# controls.net
KiCad netlist of a schematic drawn in Altium Designer
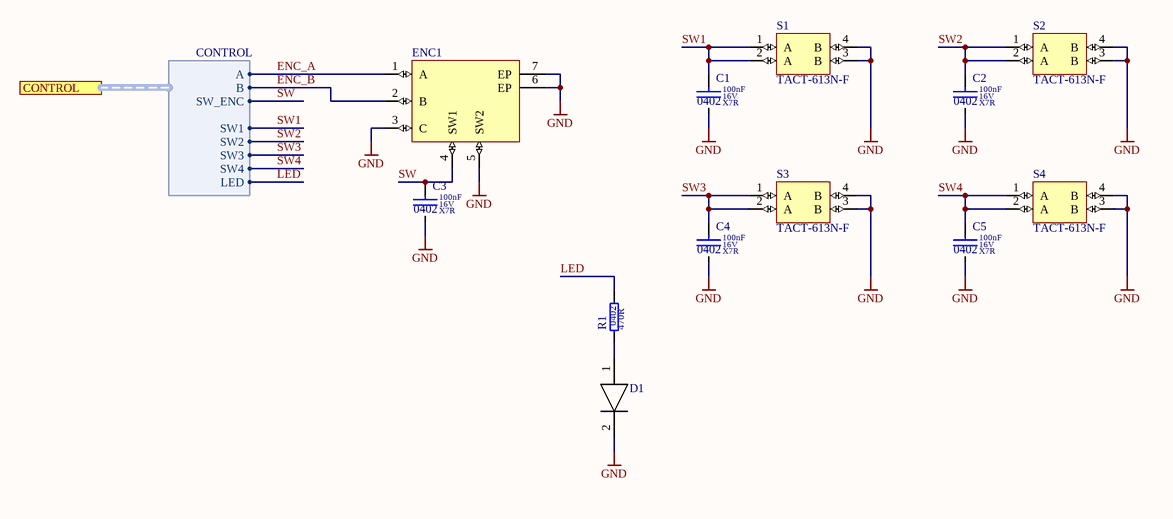
[diagram p0: controls.SchDoc]

(export (version "E")
  (design (tool "Eeschema 10.0.6"))
  (components
    (comp (ref "C1")
      (value "100nF")
      (footprint "C_0402_1005")
      (description "Capacitor")
      (fields
        (field (name "DIELECTRIC") "X7R")
        (field (name "VOLTAGE") "16V")
        (field (name "SCH_FOOTPRINT") "0402")
        (field (name "PART NUMBER") "C_100nF_16V_X7R_0402_10")
        (field (name "MANUFACTURER") "Murata")
      )
      (libsource (lib "Library") (part "C"))
    )
    (comp (ref "C2")
      (value "100nF")
      (footprint "C_0402_1005")
      (description "Capacitor")
      (fields
        (field (name "DIELECTRIC") "X7R")
        (field (name "VOLTAGE") "16V")
        (field (name "SCH_FOOTPRINT") "0402")
        (field (name "PART NUMBER") "C_100nF_16V_X7R_0402_10")
        (field (name "MANUFACTURER") "Murata")
      )
      (libsource (lib "Library") (part "C"))
    )
    (comp (ref "C3")
      (value "100nF")
      (footprint "C_0402_1005")
      (description "Capacitor")
      (fields
        (field (name "DIELECTRIC") "X7R")
        (field (name "VOLTAGE") "16V")
        (field (name "SCH_FOOTPRINT") "0402")
        (field (name "PART NUMBER") "C_100nF_16V_X7R_0402_10")
        (field (name "MANUFACTURER") "Murata")
      )
      (libsource (lib "Library") (part "C"))
    )
    (comp (ref "C4")
      (value "100nF")
      (footprint "C_0402_1005")
      (description "Capacitor")
      (fields
        (field (name "DIELECTRIC") "X7R")
        (field (name "VOLTAGE") "16V")
        (field (name "SCH_FOOTPRINT") "0402")
        (field (name "PART NUMBER") "C_100nF_16V_X7R_0402_10")
        (field (name "MANUFACTURER") "Murata")
      )
      (libsource (lib "Library") (part "C"))
    )
    (comp (ref "C5")
      (value "100nF")
      (footprint "C_0402_1005")
      (description "Capacitor")
      (fields
        (field (name "DIELECTRIC") "X7R")
        (field (name "VOLTAGE") "16V")
        (field (name "SCH_FOOTPRINT") "0402")
        (field (name "PART NUMBER") "C_100nF_16V_X7R_0402_10")
        (field (name "MANUFACTURER") "Murata")
      )
      (libsource (lib "Library") (part "C"))
    )
    (comp (ref "D1")
      (value "LED_5mm")
      (footprint "LED_5mm")
      (description "LED_5mm Diameter")
      (libsource (lib "soldering_station") (part "LED_5mm"))
    )
    (comp (ref "ENC1")
      (value "Wurth Elektronik 482016514001")
      (footprint "ENCODER")
      (libsource (lib "soldering_station") (part "ENCODER"))
    )
    (comp (ref "R1")
      (value "470R")
      (footprint "R_0402_1005")
      (fields
        (field (name "SCH_FOOTPRINT") "0402")
        (field (name "PART NUMBER") "R_470R_0402_1")
        (field (name "VOLTAGE") "50V")
        (field (name "POWER") "63mW")
      )
      (libsource (lib "Library") (part "R"))
    )
    (comp (ref "S1")
      (value "TACT-613N-F")
      (footprint "TACT-613N-F")
      (libsource (lib "soldering_station") (part "TACT-613N-F"))
    )
    (comp (ref "S2")
      (value "TACT-613N-F")
      (footprint "TACT-613N-F")
      (libsource (lib "soldering_station") (part "TACT-613N-F"))
    )
    (comp (ref "S3")
      (value "TACT-613N-F")
      (footprint "TACT-613N-F")
      (libsource (lib "soldering_station") (part "TACT-613N-F"))
    )
    (comp (ref "S4")
      (value "TACT-613N-F")
      (footprint "TACT-613N-F")
      (libsource (lib "soldering_station") (part "TACT-613N-F"))
    )
  )
  (nets
    (net (code "2") (name "/ENC_A") (class "Default")
      (node (ref "ENC1") (pin "1") (pinfunction "A_1") (pintype "bidirectional"))
    )
    (net (code "3") (name "/ENC_B") (class "Default")
      (node (ref "ENC1") (pin "2") (pinfunction "B_2") (pintype "bidirectional"))
    )
    (net (code "4") (name "/LED") (class "Default")
      (node (ref "R1") (pin "2") (pinfunction "2_2") (pintype "passive"))
    )
    (net (code "5") (name "/SW") (class "Default")
      (node (ref "C3") (pin "1") (pinfunction "1_1") (pintype "passive"))
      (node (ref "ENC1") (pin "4") (pinfunction "SW1_4") (pintype "bidirectional"))
    )
    (net (code "6") (name "/SW1") (class "Default")
      (node (ref "C1") (pin "1") (pinfunction "1_1") (pintype "passive"))
      (node (ref "S1") (pin "1") (pinfunction "A_1") (pintype "bidirectional"))
      (node (ref "S1") (pin "2") (pinfunction "A_2") (pintype "bidirectional"))
    )
    (net (code "7") (name "/SW2") (class "Default")
      (node (ref "C2") (pin "1") (pinfunction "1_1") (pintype "passive"))
      (node (ref "S2") (pin "1") (pinfunction "A_1") (pintype "bidirectional"))
      (node (ref "S2") (pin "2") (pinfunction "A_2") (pintype "bidirectional"))
    )
    (net (code "8") (name "/SW3") (class "Default")
      (node (ref "C4") (pin "1") (pinfunction "1_1") (pintype "passive"))
      (node (ref "S3") (pin "1") (pinfunction "A_1") (pintype "bidirectional"))
      (node (ref "S3") (pin "2") (pinfunction "A_2") (pintype "bidirectional"))
    )
    (net (code "9") (name "/SW4") (class "Default")
      (node (ref "C5") (pin "1") (pinfunction "1_1") (pintype "passive"))
      (node (ref "S4") (pin "1") (pinfunction "A_1") (pintype "bidirectional"))
      (node (ref "S4") (pin "2") (pinfunction "A_2") (pintype "bidirectional"))
    )
    (net (code "11") (name "GND") (class "Default")
      (node (ref "C1") (pin "2") (pinfunction "2_2") (pintype "passive"))
      (node (ref "C2") (pin "2") (pinfunction "2_2") (pintype "passive"))
      (node (ref "C3") (pin "2") (pinfunction "2_2") (pintype "passive"))
      (node (ref "C4") (pin "2") (pinfunction "2_2") (pintype "passive"))
      (node (ref "C5") (pin "2") (pinfunction "2_2") (pintype "passive"))
      (node (ref "D1") (pin "2") (pinfunction "Cathode_2") (pintype "passive"))
      (node (ref "ENC1") (pin "3") (pinfunction "C_3") (pintype "bidirectional"))
      (node (ref "ENC1") (pin "5") (pinfunction "SW2_5") (pintype "bidirectional"))
      (node (ref "ENC1") (pin "6") (pinfunction "EP_6") (pintype "passive"))
      (node (ref "ENC1") (pin "7") (pinfunction "EP_7") (pintype "passive"))
      (node (ref "S1") (pin "3") (pinfunction "B_3") (pintype "bidirectional"))
      (node (ref "S1") (pin "4") (pinfunction "B_4") (pintype "bidirectional"))
      (node (ref "S2") (pin "3") (pinfunction "B_3") (pintype "bidirectional"))
      (node (ref "S2") (pin "4") (pinfunction "B_4") (pintype "bidirectional"))
      (node (ref "S3") (pin "3") (pinfunction "B_3") (pintype "bidirectional"))
      (node (ref "S3") (pin "4") (pinfunction "B_4") (pintype "bidirectional"))
      (node (ref "S4") (pin "3") (pinfunction "B_3") (pintype "bidirectional"))
      (node (ref "S4") (pin "4") (pinfunction "B_4") (pintype "bidirectional"))
    )
    (net (code "12") (name "Net-(D1-Anode)") (class "Default")
      (node (ref "D1") (pin "1") (pinfunction "Anode_1") (pintype "passive"))
      (node (ref "R1") (pin "1") (pinfunction "1_1") (pintype "passive"))
    )
  )
)
